# pca10040_sheet5_power_supply.net
KiCad netlist of a schematic drawn in Altium Designer
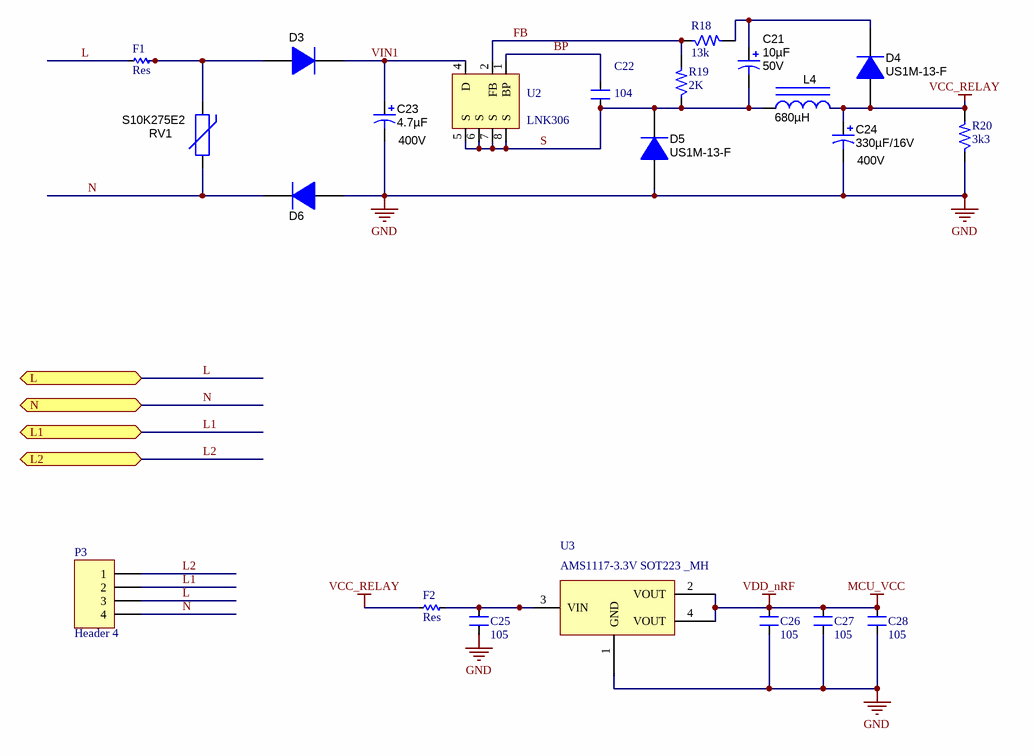
[diagram p0: pca10040_sheet5_power_supply.SchDoc]

(export (version "E")
  (design (tool "Eeschema 10.0.6"))
  (components
    (comp (ref "C21")
      (value "ECA-1HHG100")
      (footprint "PcbLib1:NHG_500x1100")
      (description "CAP, AL, 10 µF, 50 V, +/- 20%, TH")
      (fields
        (field (name "VALUEDISPLAYED") "10µF")
        (field (name "MANUFACTURER") "Panasonic")
        (field (name "VALUE2") "50V")
        (field (name "PUBLISHER") "Texas Instruments")
      )
      (libsource (lib "Capacitor_Aluminum") (part "ECA-1HHG100"))
    )
    (comp (ref "C22")
      (value "104")
      (footprint "0805_HV")
      (description "Cap SMD")
      (libsource (lib "hatcatbietbay") (part "CM"))
    )
    (comp (ref "C23")
      (value "400AX6R8M8x11")
      (footprint "PcbLib1:PANACAP-G-GENERIC")
      (description "CAP, AL, 6.8uF, 400V, +/-20%, TH")
      (fields
        (field (name "VALUEDISPLAYED") "4.7µF")
        (field (name "MANUFACTURER") "Rubycon")
        (field (name "VALUE2") "400V")
        (field (name "PUBLISHER") "Texas Instruments")
      )
      (libsource (lib "Capacitor_Aluminum") (part "400AX6R8M8x11"))
    )
    (comp (ref "C24")
      (value "400AX6R8M8x11")
      (footprint "PcbLib1:CAPPRD350W60D800H1100")
      (description "CAP, AL, 6.8uF, 400V, +/-20%, TH")
      (fields
        (field (name "VALUEDISPLAYED") "330µF/16V")
        (field (name "MANUFACTURER") "Rubycon")
        (field (name "VALUE2") "400V")
        (field (name "PUBLISHER") "Texas Instruments")
      )
      (libsource (lib "Capacitor_Aluminum") (part "400AX6R8M8x11"))
    )
    (comp (ref "C25")
      (value "105")
      (footprint "0805_HV")
      (description "Cap SMD")
      (libsource (lib "hatcatbietbay") (part "CM"))
    )
    (comp (ref "C26")
      (value "105")
      (footprint "0805_HV")
      (description "Cap SMD")
      (libsource (lib "hatcatbietbay") (part "CM"))
    )
    (comp (ref "C27")
      (value "105")
      (footprint "0805_HV")
      (description "Cap SMD")
      (libsource (lib "hatcatbietbay") (part "CM"))
    )
    (comp (ref "C28")
      (value "105")
      (footprint "0805_HV")
      (description "Cap SMD")
      (libsource (lib "hatcatbietbay") (part "CM"))
    )
    (comp (ref "D3")
      (value "US1M-13-F")
      (footprint "PcbLib1:SMB")
      (description "Diode, Ultrafast, 600V, 1A, SMB")
      (fields (field (name "MANUFACTURER") "Diodes Inc.") (field (name "PUBLISHER") "Texas Instruments"))
      (libsource (lib "Diode") (part "MURS160-13-F"))
    )
    (comp (ref "D4")
      (value "US1M-13-F")
      (footprint "PcbLib1:SMB")
      (description "Diode, Ultrafast, 600V, 1A, SMB")
      (fields
        (field (name "PARTNUMBER") "US1M-13-F")
        (field (name "MANUFACTURER") "Diodes Inc.")
        (field (name "PUBLISHER") "Texas Instruments")
      )
      (libsource (lib "Diode") (part "MURS160-13-F"))
    )
    (comp (ref "D5")
      (value "US1M-13-F")
      (footprint "PcbLib1:SMB")
      (description "Diode, Ultrafast, 600V, 1A, SMB")
      (fields
        (field (name "PARTNUMBER") "US1M-13-F")
        (field (name "MANUFACTURER") "Diodes Inc.")
        (field (name "PUBLISHER") "Texas Instruments")
      )
      (libsource (lib "Diode") (part "MURS160-13-F"))
    )
    (comp (ref "D6")
      (value "US1M-13-F")
      (footprint "PcbLib1:SMB")
      (description "Diode, Ultrafast, 600V, 1A, SMB")
      (fields (field (name "MANUFACTURER") "Diodes Inc.") (field (name "PUBLISHER") "Texas Instruments"))
      (libsource (lib "Diode") (part "MURS160-13-F"))
    )
    (comp (ref "F1")
      (value "Res")
      (footprint "1206")
      (description "Resistor")
      (fields
        (field (name "MANUFACTURER") "Generic Components")
        (field (name "PUBLISHER") "Altium Hobart Technology Centre")
      )
      (libsource (lib "LIBRARY") (part "Res-SMD"))
    )
    (comp (ref "F2")
      (value "Res")
      (footprint "1206")
      (description "Resistor")
      (fields
        (field (name "MANUFACTURER") "Generic Components")
        (field (name "PUBLISHER") "Altium Hobart Technology Centre")
      )
      (libsource (lib "LIBRARY") (part "Res-SMD"))
    )
    (comp (ref "L4")
      (value "7447480331")
      (footprint "PcbLib1:IND_WE-TI_8095")
      (description "Inductor, Wirewound, Ferrite, 330 µH, 1.4 A, 0.3 ohm, TH")
      (fields
        (field (name "VALUEDISPLAYED") "680µH")
        (field (name "MANUFACTURER") "Wurth Elektronik")
        (field (name "PUBLISHER") "Texas Instruments")
      )
      (libsource (lib "Inductor_Wurth") (part "7447480331"))
    )
    (comp (ref "P3")
      (value "Header 4")
      (footprint "CONWALL_SWITH")
      (description "Header, 4-Pin")
      (fields (field (name "PUBLISHER") "Altium Limited"))
      (libsource (lib "Miscellaneous Connectors") (part "Header 4"))
    )
    (comp (ref "R18")
      (value "13k")
      (footprint "0805_HV")
      (description "Resistor 1/4W")
      (libsource (lib "hatcatbietbay") (part "R"))
    )
    (comp (ref "R19")
      (value "2K")
      (footprint "0805_HV")
      (description "Resistor 1/4W")
      (libsource (lib "hatcatbietbay") (part "R"))
    )
    (comp (ref "R20")
      (value "3k3")
      (footprint "0805_HV")
      (description "Resistor 1/4W")
      (libsource (lib "hatcatbietbay") (part "R"))
    )
    (comp (ref "RV1")
      (value "S10K275E2")
      (footprint "PcbLib1:VAR_S10K275E2")
      (description "Varistor 275V RMS 10MM Radial, TH")
      (fields
        (field (name "MANUFACTURER") "EPCOS Inc")
        (field (name "SYMBOLCREATOR") "a0412235")
        (field (name "PUBLISHER") "Texas Instruments")
      )
      (libsource (lib "Other_Passive") (part "S10K275E2"))
    )
    (comp (ref "U2") (value "LNK306") (footprint "SOP 7") (libsource (lib "LNK304") (part "Component_1")))
    (comp (ref "U3")
      (value "AMS1117-3.3V SOT223 _MH")
      (footprint "SOT223")
      (libsource (lib "MH_DA_THU_VIEN_16122016") (part "AMS1117-3.3V SOT223 _MH"))
    )
  )
  (nets
    (net (code "1") (name "/BP") (class "Default")
      (node (ref "C22") (pin "2") (pinfunction "2_2") (pintype "passive"))
      (node (ref "U2") (pin "1") (pinfunction "BP_1") (pintype "passive"))
    )
    (net (code "2") (name "/FB") (class "Default")
      (node (ref "R18") (pin "1") (pinfunction "1_1") (pintype "passive"))
      (node (ref "R19") (pin "2") (pinfunction "2_2") (pintype "passive"))
      (node (ref "U2") (pin "2") (pinfunction "FB_2") (pintype "passive"))
    )
    (net (code "3") (name "/L") (class "Default")
      (node (ref "F1") (pin "2") (pinfunction "2_2") (pintype "passive"))
      (node (ref "P3") (pin "3") (pinfunction "3_3") (pintype "passive"))
    )
    (net (code "4") (name "/L1") (class "Default")
      (node (ref "P3") (pin "2") (pinfunction "2_2") (pintype "passive"))
    )
    (net (code "5") (name "/L2") (class "Default")
      (node (ref "P3") (pin "1") (pinfunction "1_1") (pintype "passive"))
    )
    (net (code "6") (name "/N") (class "Default")
      (node (ref "D6") (pin "1") (pinfunction "K_1") (pintype "passive"))
      (node (ref "P3") (pin "4") (pinfunction "4_4") (pintype "passive"))
      (node (ref "RV1") (pin "1") (pinfunction "1_1") (pintype "passive"))
    )
    (net (code "7") (name "/S") (class "Default")
      (node (ref "C21") (pin "2") (pinfunction "-_2") (pintype "passive"))
      (node (ref "C22") (pin "1") (pinfunction "1_1") (pintype "passive"))
      (node (ref "D5") (pin "1") (pinfunction "K_1") (pintype "passive"))
      (node (ref "L4") (pin "1") (pinfunction "1_1") (pintype "passive"))
      (node (ref "R19") (pin "1") (pinfunction "1_1") (pintype "passive"))
      (node (ref "U2") (pin "5") (pinfunction "S_5") (pintype "passive"))
      (node (ref "U2") (pin "6") (pinfunction "S_6") (pintype "passive"))
      (node (ref "U2") (pin "7") (pinfunction "S_7") (pintype "passive"))
      (node (ref "U2") (pin "8") (pinfunction "S_8") (pintype "passive"))
    )
    (net (code "8") (name "/VIN1") (class "Default")
      (node (ref "C23") (pin "1") (pinfunction "+_1") (pintype "passive"))
      (node (ref "D3") (pin "1") (pinfunction "K_1") (pintype "passive"))
      (node (ref "U2") (pin "4") (pinfunction "D_4") (pintype "passive"))
    )
    (net (code "9") (name "GND") (class "Default")
      (node (ref "C23") (pin "2") (pinfunction "-_2") (pintype "passive"))
      (node (ref "C24") (pin "2") (pinfunction "-_2") (pintype "passive"))
      (node (ref "C25") (pin "1") (pinfunction "1_1") (pintype "passive"))
      (node (ref "C26") (pin "1") (pinfunction "1_1") (pintype "passive"))
      (node (ref "C27") (pin "1") (pinfunction "1_1") (pintype "passive"))
      (node (ref "C28") (pin "1") (pinfunction "1_1") (pintype "passive"))
      (node (ref "D5") (pin "2") (pinfunction "A_2") (pintype "passive"))
      (node (ref "D6") (pin "2") (pinfunction "A_2") (pintype "passive"))
      (node (ref "R20") (pin "1") (pinfunction "1_1") (pintype "passive"))
      (node (ref "U3") (pin "1") (pinfunction "GND_1") (pintype "passive"))
    )
    (net (code "10") (name "MCU_VCC") (class "Default")
      (node (ref "C26") (pin "2") (pinfunction "2_2") (pintype "passive"))
      (node (ref "C27") (pin "2") (pinfunction "2_2") (pintype "passive"))
      (node (ref "C28") (pin "2") (pinfunction "2_2") (pintype "passive"))
      (node (ref "U3") (pin "2") (pinfunction "VOUT_2") (pintype "passive"))
      (node (ref "U3") (pin "4") (pinfunction "VOUT_4") (pintype "passive"))
    )
    (net (code "11") (name "Net-(C21-+)") (class "Default")
      (node (ref "C21") (pin "1") (pinfunction "+_1") (pintype "passive"))
      (node (ref "D4") (pin "1") (pinfunction "K_1") (pintype "passive"))
      (node (ref "R18") (pin "2") (pinfunction "2_2") (pintype "passive"))
    )
    (net (code "12") (name "Net-(D3-A)") (class "Default")
      (node (ref "D3") (pin "2") (pinfunction "A_2") (pintype "passive"))
      (node (ref "F1") (pin "1") (pinfunction "1_1") (pintype "passive"))
      (node (ref "RV1") (pin "2") (pinfunction "2_2") (pintype "passive"))
    )
    (net (code "13") (name "Net-(U3-VIN)") (class "Default")
      (node (ref "C25") (pin "2") (pinfunction "2_2") (pintype "passive"))
      (node (ref "F2") (pin "1") (pinfunction "1_1") (pintype "passive"))
      (node (ref "U3") (pin "3") (pinfunction "VIN_3") (pintype "passive"))
    )
    (net (code "14") (name "VCC_RELAY") (class "Default")
      (node (ref "C24") (pin "1") (pinfunction "+_1") (pintype "passive"))
      (node (ref "D4") (pin "2") (pinfunction "A_2") (pintype "passive"))
      (node (ref "F2") (pin "2") (pinfunction "2_2") (pintype "passive"))
      (node (ref "L4") (pin "2") (pinfunction "2_2") (pintype "passive"))
      (node (ref "R20") (pin "2") (pinfunction "2_2") (pintype "passive"))
    )
  )
)
